# GasSensorCentral_v1_1.net
KiCad netlist of a schematic drawn in EAGLE
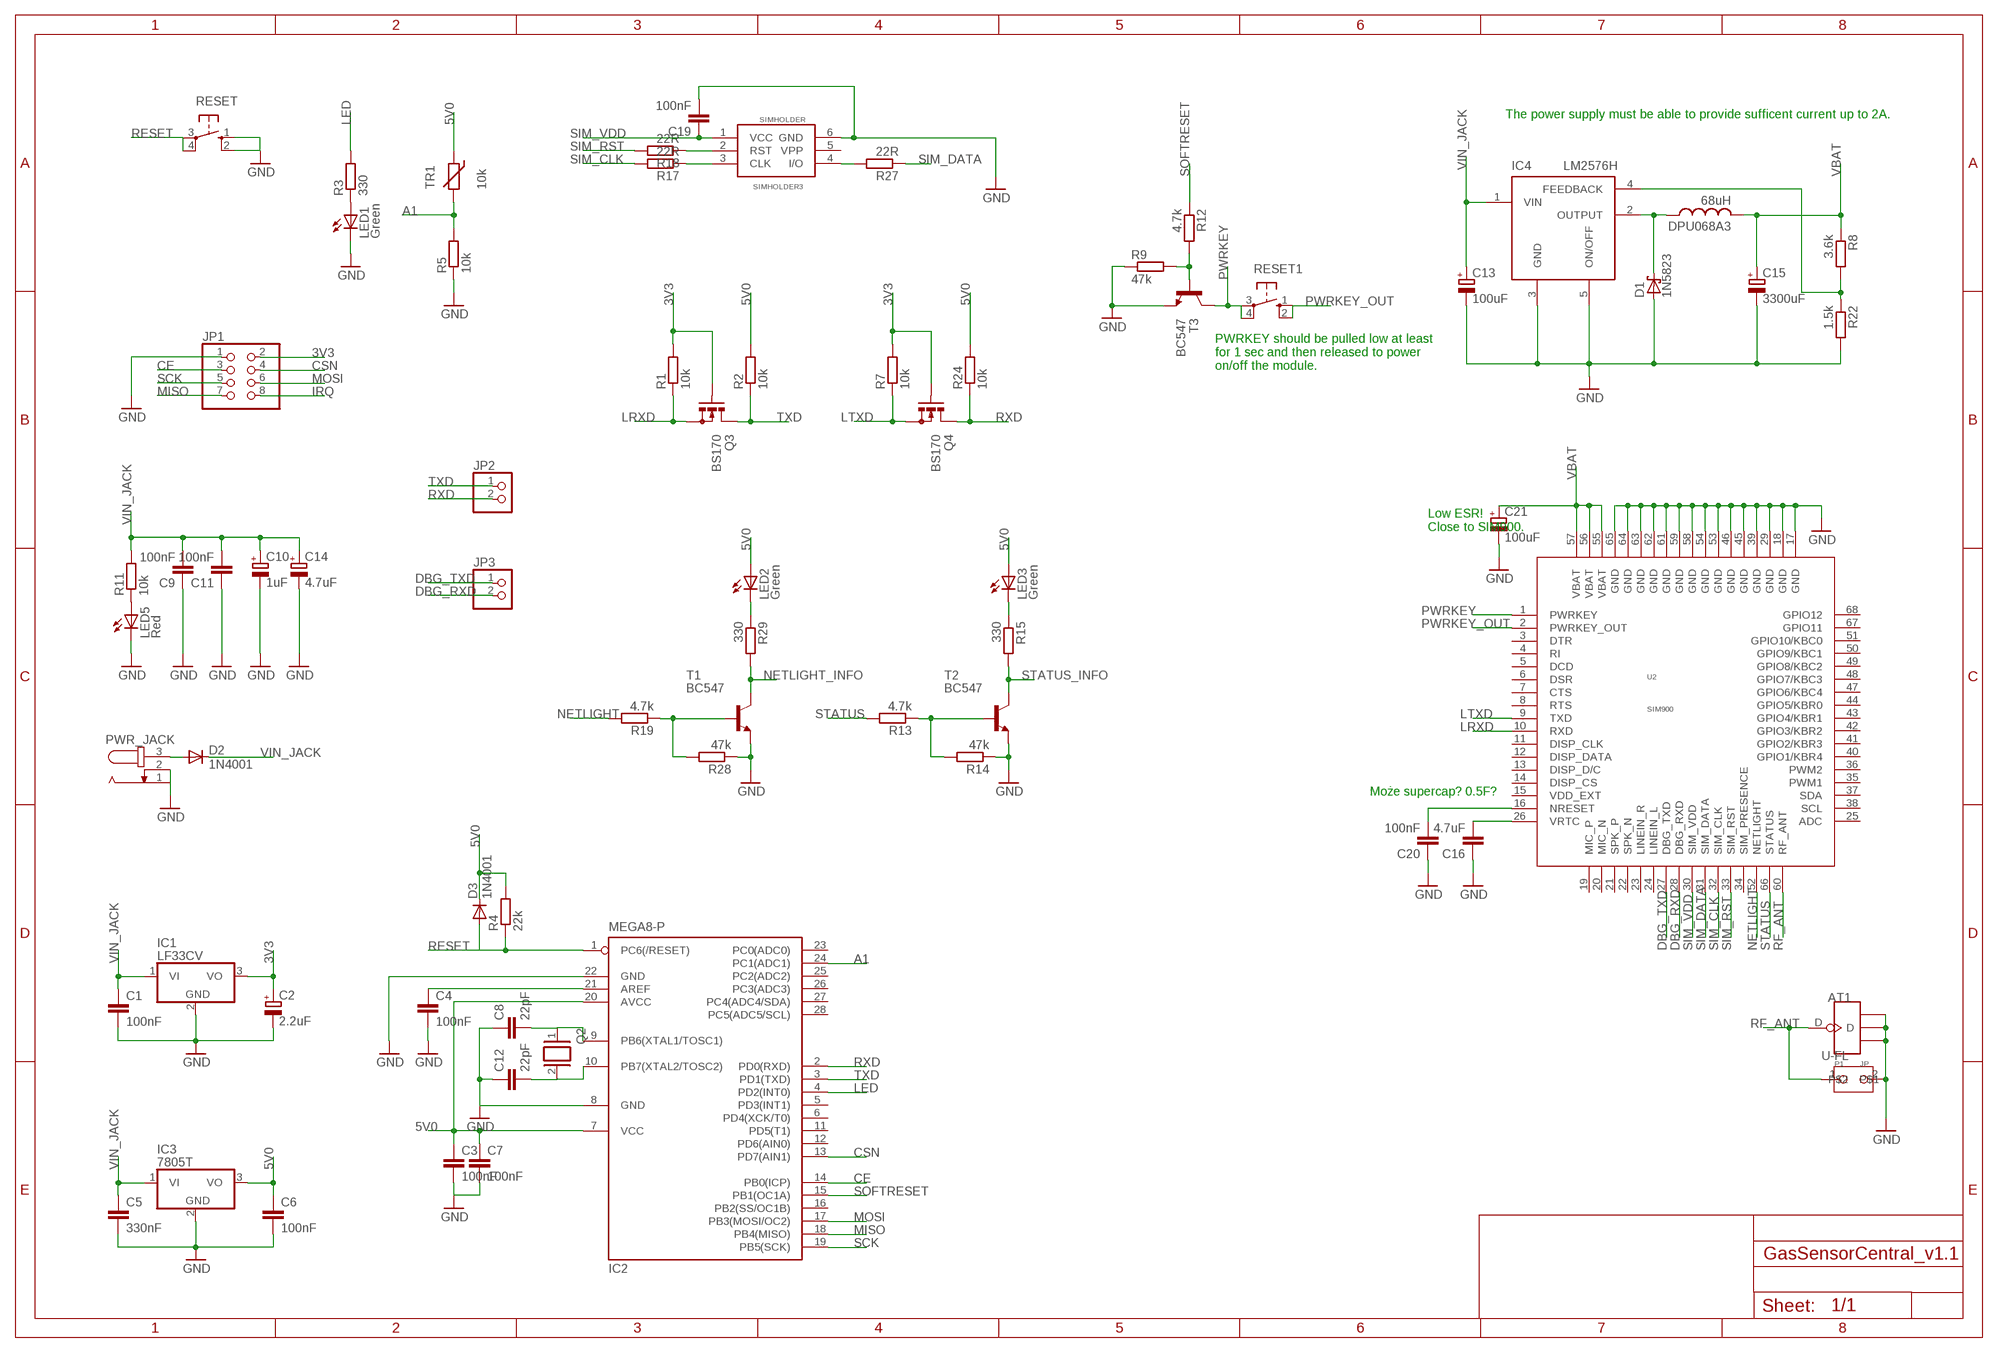
[diagram p0: schematic, sheet 1]

(export (version "E")
  (design (tool "Eeschema 10.0.6"))
  (components
    (comp (ref "AT1")
      (value "U-FL")
      (footprint "eagle-import:4P-U-FL")
      (libsource (lib "eagle-import") (part "ANTENNA-U-FL"))
    )
    (comp (ref "C1")
      (value "100nF")
      (footprint "eagle-import:C025-025X050")
      (libsource (lib "eagle-import") (part "C-EU025-025X050"))
    )
    (comp (ref "C2")
      (value "2.2uF")
      (footprint "eagle-import:E2,5-5")
      (libsource (lib "eagle-import") (part "CPOL-EUE2.5-5"))
    )
    (comp (ref "C3")
      (value "100nF")
      (footprint "eagle-import:C025-025X050")
      (libsource (lib "eagle-import") (part "C-EU025-025X050"))
    )
    (comp (ref "C4")
      (value "100nF")
      (footprint "eagle-import:C025-025X050")
      (libsource (lib "eagle-import") (part "C-EU025-025X050"))
    )
    (comp (ref "C5")
      (value "330nF")
      (footprint "eagle-import:C025-025X050")
      (libsource (lib "eagle-import") (part "C-EU025-025X050"))
    )
    (comp (ref "C6")
      (value "100nF")
      (footprint "eagle-import:C025-025X050")
      (libsource (lib "eagle-import") (part "C-EU025-025X050"))
    )
    (comp (ref "C7")
      (value "100nF")
      (footprint "eagle-import:C025-025X050")
      (libsource (lib "eagle-import") (part "C-EU025-025X050"))
    )
    (comp (ref "C8")
      (value "22pF")
      (footprint "eagle-import:C025-025X050")
      (libsource (lib "eagle-import") (part "C-EU025-025X050"))
    )
    (comp (ref "C9")
      (value "100nF")
      (footprint "eagle-import:C025-025X050")
      (libsource (lib "eagle-import") (part "C-EU025-025X050"))
    )
    (comp (ref "C10")
      (value "1uF")
      (footprint "eagle-import:E2,5-5")
      (libsource (lib "eagle-import") (part "CPOL-EUE2.5-5"))
    )
    (comp (ref "C11")
      (value "100nF")
      (footprint "eagle-import:C025-025X050")
      (libsource (lib "eagle-import") (part "C-EU025-025X050"))
    )
    (comp (ref "C12")
      (value "22pF")
      (footprint "eagle-import:C025-025X050")
      (libsource (lib "eagle-import") (part "C-EU025-025X050"))
    )
    (comp (ref "C13")
      (value "100uF")
      (footprint "eagle-import:E2,5-5")
      (libsource (lib "eagle-import") (part "CPOL-EUE2.5-5"))
    )
    (comp (ref "C14")
      (value "4.7uF")
      (footprint "eagle-import:E2,5-5")
      (libsource (lib "eagle-import") (part "CPOL-EUE2.5-5"))
    )
    (comp (ref "C15")
      (value "3300uF")
      (footprint "eagle-import:E3,5-10")
      (libsource (lib "eagle-import") (part "CPOL-EUE3.5-10"))
    )
    (comp (ref "C16")
      (value "4.7uF")
      (footprint "eagle-import:C025-025X050")
      (libsource (lib "eagle-import") (part "C-EU025-025X050"))
    )
    (comp (ref "C19")
      (value "100nF")
      (footprint "eagle-import:C025-025X050")
      (libsource (lib "eagle-import") (part "C-EU025-025X050"))
    )
    (comp (ref "C20")
      (value "100nF")
      (footprint "eagle-import:C025-025X050")
      (libsource (lib "eagle-import") (part "C-EU025-025X050"))
    )
    (comp (ref "C21")
      (value "100uF")
      (footprint "eagle-import:E2,5-5")
      (libsource (lib "eagle-import") (part "CPOL-EUE2.5-5"))
    )
    (comp (ref "D1")
      (value "1N5823")
      (footprint "eagle-import:DO41-7.6")
      (libsource (lib "eagle-import") (part "1N5817-B"))
    )
    (comp (ref "D2")
      (value "1N4001")
      (footprint "eagle-import:DO41-10")
      (libsource (lib "eagle-import") (part "1N4004"))
    )
    (comp (ref "D3")
      (value "1N4001")
      (footprint "eagle-import:DO41-10")
      (libsource (lib "eagle-import") (part "1N4004"))
    )
    (comp (ref "DPU068A3")
      (value "68uH")
      (footprint "eagle-import:TJ3-U1")
      (libsource (lib "eagle-import") (part "L-USTJ3-U1"))
    )
    (comp (ref "IC1")
      (value "LF33CV")
      (footprint "eagle-import:TO220H")
      (libsource (lib "eagle-import") (part "78T05"))
    )
    (comp (ref "IC2")
      (value "MEGA8-P")
      (footprint "eagle-import:DIL28-3")
      (libsource (lib "eagle-import") (part "MEGA8-P"))
    )
    (comp (ref "IC3")
      (value "7805T")
      (footprint "eagle-import:TO220H")
      (libsource (lib "eagle-import") (part "78T05"))
    )
    (comp (ref "IC4")
      (value "LM2576H")
      (footprint "eagle-import:TO220-52")
      (libsource (lib "eagle-import") (part "LM2576H"))
    )
    (comp (ref "JP1")
      (value "PINHD-2X4")
      (footprint "eagle-import:2X04")
      (libsource (lib "eagle-import") (part "PINHD-2X4"))
    )
    (comp (ref "JP2")
      (value "PINHD-1X2")
      (footprint "eagle-import:1X02")
      (libsource (lib "eagle-import") (part "PINHD-1X2"))
    )
    (comp (ref "JP3")
      (value "PINHD-1X2")
      (footprint "eagle-import:1X02")
      (libsource (lib "eagle-import") (part "PINHD-1X2"))
    )
    (comp (ref "LED1")
      (value "Green")
      (footprint "eagle-import:LED3MM")
      (libsource (lib "eagle-import") (part "LED3MM"))
    )
    (comp (ref "LED2")
      (value "Green")
      (footprint "eagle-import:LED3MM")
      (libsource (lib "eagle-import") (part "LED3MM"))
    )
    (comp (ref "LED3")
      (value "Green")
      (footprint "eagle-import:LED3MM")
      (libsource (lib "eagle-import") (part "LED3MM"))
    )
    (comp (ref "LED5")
      (value "Red")
      (footprint "eagle-import:LED3MM")
      (libsource (lib "eagle-import") (part "LED3MM"))
    )
    (comp (ref "P1") (value "JP") (footprint "eagle-import:JP") (libsource (lib "eagle-import") (part "JP")))
    (comp (ref "PWR_JACK")
      (value "JACK-PLUG0")
      (footprint "eagle-import:SPC4077")
      (libsource (lib "eagle-import") (part "JACK-PLUG0"))
    )
    (comp (ref "Q2")
      (value "XTAL/S")
      (footprint "eagle-import:QS")
      (libsource (lib "eagle-import") (part "XTAL/S"))
    )
    (comp (ref "Q3")
      (value "BS170")
      (footprint "eagle-import:SOT54E")
      (libsource (lib "eagle-import") (part "BS170"))
    )
    (comp (ref "Q4")
      (value "BS170")
      (footprint "eagle-import:SOT54E")
      (libsource (lib "eagle-import") (part "BS170"))
    )
    (comp (ref "R1")
      (value "10k")
      (footprint "eagle-import:0207_10")
      (libsource (lib "eagle-import") (part "R-EU_0207/10"))
    )
    (comp (ref "R2")
      (value "10k")
      (footprint "eagle-import:0207_10")
      (libsource (lib "eagle-import") (part "R-EU_0207/10"))
    )
    (comp (ref "R3")
      (value "330")
      (footprint "eagle-import:0207_10")
      (libsource (lib "eagle-import") (part "R-EU_0207/10"))
    )
    (comp (ref "R4")
      (value "22k")
      (footprint "eagle-import:0207_10")
      (libsource (lib "eagle-import") (part "R-EU_0207/10"))
    )
    (comp (ref "R5")
      (value "10k")
      (footprint "eagle-import:0207_10")
      (libsource (lib "eagle-import") (part "R-EU_0207/10"))
    )
    (comp (ref "R7")
      (value "10k")
      (footprint "eagle-import:0207_10")
      (libsource (lib "eagle-import") (part "R-EU_0207/10"))
    )
    (comp (ref "R8")
      (value "3.6k")
      (footprint "eagle-import:0207_10")
      (libsource (lib "eagle-import") (part "R-EU_0207/10"))
    )
    (comp (ref "R9")
      (value "47k")
      (footprint "eagle-import:0207_10")
      (libsource (lib "eagle-import") (part "R-EU_0207/10"))
    )
    (comp (ref "R11")
      (value "10k")
      (footprint "eagle-import:0207_10")
      (libsource (lib "eagle-import") (part "R-EU_0207/10"))
    )
    (comp (ref "R12")
      (value "4.7k")
      (footprint "eagle-import:0207_10")
      (libsource (lib "eagle-import") (part "R-EU_0207/10"))
    )
    (comp (ref "R13")
      (value "4.7k")
      (footprint "eagle-import:0207_10")
      (libsource (lib "eagle-import") (part "R-EU_0207/10"))
    )
    (comp (ref "R14")
      (value "47k")
      (footprint "eagle-import:0207_10")
      (libsource (lib "eagle-import") (part "R-EU_0207/10"))
    )
    (comp (ref "R15")
      (value "330")
      (footprint "eagle-import:0207_10")
      (libsource (lib "eagle-import") (part "R-EU_0207/10"))
    )
    (comp (ref "R17")
      (value "22R")
      (footprint "eagle-import:0207_10")
      (libsource (lib "eagle-import") (part "R-EU_0207/10"))
    )
    (comp (ref "R18")
      (value "22R")
      (footprint "eagle-import:0207_10")
      (libsource (lib "eagle-import") (part "R-EU_0207/10"))
    )
    (comp (ref "R19")
      (value "4.7k")
      (footprint "eagle-import:0207_10")
      (libsource (lib "eagle-import") (part "R-EU_0207/10"))
    )
    (comp (ref "R22")
      (value "1.5k")
      (footprint "eagle-import:0207_10")
      (libsource (lib "eagle-import") (part "R-EU_0207/10"))
    )
    (comp (ref "R24")
      (value "10k")
      (footprint "eagle-import:0207_10")
      (libsource (lib "eagle-import") (part "R-EU_0207/10"))
    )
    (comp (ref "R27")
      (value "22R")
      (footprint "eagle-import:0207_10")
      (libsource (lib "eagle-import") (part "R-EU_0207/10"))
    )
    (comp (ref "R28")
      (value "47k")
      (footprint "eagle-import:0207_10")
      (libsource (lib "eagle-import") (part "R-EU_0207/10"))
    )
    (comp (ref "R29")
      (value "330")
      (footprint "eagle-import:0207_10")
      (libsource (lib "eagle-import") (part "R-EU_0207/10"))
    )
    (comp (ref "RESET")
      (value "10-XX")
      (footprint "eagle-import:B3F-10XX")
      (fields (field (name "MPN") "B3F-1000"))
      (libsource (lib "eagle-import") (part "10-XX"))
    )
    (comp (ref "RESET1")
      (value "10-XX")
      (footprint "eagle-import:B3F-10XX")
      (fields (field (name "MPN") "B3F-1000"))
      (libsource (lib "eagle-import") (part "10-XX"))
    )
    (comp (ref "SIMHOLDER")
      (value "SIMHOLDER3")
      (footprint "eagle-import:SIMHOLDER3")
      (libsource (lib "eagle-import") (part "SIMHOLDER3"))
    )
    (comp (ref "T1")
      (value "BC547")
      (footprint "eagle-import:TO92")
      (libsource (lib "eagle-import") (part "BC547"))
    )
    (comp (ref "T2")
      (value "BC547")
      (footprint "eagle-import:TO92")
      (libsource (lib "eagle-import") (part "BC547"))
    )
    (comp (ref "T3")
      (value "BC547")
      (footprint "eagle-import:TO92")
      (libsource (lib "eagle-import") (part "BC547"))
    )
    (comp (ref "TR1")
      (value "10k")
      (footprint "eagle-import:RS-2,5")
      (libsource (lib "eagle-import") (part "THERMISTOR_R-2,5"))
    )
    (comp (ref "U2")
      (value "SIM900")
      (footprint "eagle-import:SIM900")
      (libsource (lib "eagle-import") (part "SIM900"))
    )
  )
  (nets
    (net (code "1") (name "/3V3") (class "Default")
      (node (ref "C2") (pin "+") (pinfunction "+_+") (pintype "passive"))
      (node (ref "IC1") (pin "3") (pinfunction "VO_3") (pintype "passive"))
      (node (ref "JP1") (pin "2") (pinfunction "2_2") (pintype "passive"))
      (node (ref "Q3") (pin "G") (pinfunction "G_G") (pintype "passive"))
      (node (ref "Q4") (pin "G") (pinfunction "G_G") (pintype "passive"))
      (node (ref "R1") (pin "2") (pinfunction "2_2") (pintype "passive"))
      (node (ref "R7") (pin "2") (pinfunction "2_2") (pintype "passive"))
    )
    (net (code "2") (name "/5V0") (class "Default")
      (node (ref "C3") (pin "1") (pinfunction "1_1") (pintype "passive"))
      (node (ref "C6") (pin "1") (pinfunction "1_1") (pintype "passive"))
      (node (ref "C7") (pin "1") (pinfunction "1_1") (pintype "passive"))
      (node (ref "D3") (pin "C") (pinfunction "C_C") (pintype "passive"))
      (node (ref "IC2") (pin "20") (pinfunction "AVCC_20") (pintype "power_in"))
      (node (ref "IC2") (pin "7") (pinfunction "VCC_7") (pintype "power_in"))
      (node (ref "IC3") (pin "3") (pinfunction "VO_3") (pintype "passive"))
      (node (ref "LED2") (pin "A") (pinfunction "A_A") (pintype "passive"))
      (node (ref "LED3") (pin "A") (pinfunction "A_A") (pintype "passive"))
      (node (ref "R2") (pin "2") (pinfunction "2_2") (pintype "passive"))
      (node (ref "R24") (pin "2") (pinfunction "2_2") (pintype "passive"))
      (node (ref "R4") (pin "2") (pinfunction "2_2") (pintype "passive"))
      (node (ref "TR1") (pin "1") (pinfunction "1_1") (pintype "passive"))
    )
    (net (code "3") (name "/A1") (class "Default")
      (node (ref "IC2") (pin "24") (pinfunction "PC1(ADC1)_24") (pintype "bidirectional"))
      (node (ref "R5") (pin "2") (pinfunction "2_2") (pintype "passive"))
      (node (ref "TR1") (pin "2") (pinfunction "2_2") (pintype "passive"))
    )
    (net (code "4") (name "/CE") (class "Default")
      (node (ref "IC2") (pin "14") (pinfunction "PB0(ICP)_14") (pintype "bidirectional"))
      (node (ref "JP1") (pin "3") (pinfunction "3_3") (pintype "passive"))
    )
    (net (code "5") (name "/CSN") (class "Default")
      (node (ref "IC2") (pin "13") (pinfunction "PD7(AIN1)_13") (pintype "bidirectional"))
      (node (ref "JP1") (pin "4") (pinfunction "4_4") (pintype "passive"))
    )
    (net (code "6") (name "/DBG_RXD") (class "Default")
      (node (ref "JP3") (pin "2") (pinfunction "2_2") (pintype "passive"))
      (node (ref "U2") (pin "28") (pinfunction "DBG_RXD_28") (pintype "input"))
    )
    (net (code "7") (name "/DBG_TXD") (class "Default")
      (node (ref "JP3") (pin "1") (pinfunction "1_1") (pintype "passive"))
      (node (ref "U2") (pin "27") (pinfunction "DBG_TXD_27") (pintype "output"))
    )
    (net (code "8") (name "/IRQ") (class "Default")
      (node (ref "JP1") (pin "8") (pinfunction "8_8") (pintype "passive"))
    )
    (net (code "9") (name "/LED") (class "Default")
      (node (ref "IC2") (pin "4") (pinfunction "PD2(INT0)_4") (pintype "bidirectional"))
      (node (ref "R3") (pin "2") (pinfunction "2_2") (pintype "passive"))
    )
    (net (code "10") (name "/LRXD") (class "Default")
      (node (ref "Q3") (pin "S") (pinfunction "S_S") (pintype "passive"))
      (node (ref "R1") (pin "1") (pinfunction "1_1") (pintype "passive"))
      (node (ref "U2") (pin "10") (pinfunction "RXD_10") (pintype "input"))
    )
    (net (code "11") (name "/LTXD") (class "Default")
      (node (ref "Q4") (pin "S") (pinfunction "S_S") (pintype "passive"))
      (node (ref "R7") (pin "1") (pinfunction "1_1") (pintype "passive"))
      (node (ref "U2") (pin "9") (pinfunction "TXD_9") (pintype "output"))
    )
    (net (code "12") (name "/MISO") (class "Default")
      (node (ref "IC2") (pin "18") (pinfunction "PB4(MISO)_18") (pintype "bidirectional"))
      (node (ref "JP1") (pin "7") (pinfunction "7_7") (pintype "passive"))
    )
    (net (code "13") (name "/MOSI") (class "Default")
      (node (ref "IC2") (pin "17") (pinfunction "PB3(MOSI/OC2)_17") (pintype "bidirectional"))
      (node (ref "JP1") (pin "6") (pinfunction "6_6") (pintype "passive"))
    )
    (net (code "14") (name "/NETLIGHT") (class "Default")
      (node (ref "R19") (pin "2") (pinfunction "2_2") (pintype "passive"))
      (node (ref "U2") (pin "52") (pinfunction "NETLIGHT_52") (pintype "output"))
    )
    (net (code "15") (name "/NETLIGHT_INFO") (class "Default")
      (node (ref "R29") (pin "2") (pinfunction "2_2") (pintype "passive"))
      (node (ref "T1") (pin "3") (pinfunction "C_3") (pintype "passive"))
    )
    (net (code "16") (name "/PWRKEY") (class "Default")
      (node (ref "RESET1") (pin "3") (pinfunction "P_3") (pintype "passive"))
      (node (ref "RESET1") (pin "4") (pinfunction "P1_4") (pintype "passive"))
      (node (ref "T3") (pin "3") (pinfunction "C_3") (pintype "passive"))
      (node (ref "U2") (pin "1") (pinfunction "PWRKEY_1") (pintype "input"))
    )
    (net (code "17") (name "/PWRKEY_OUT") (class "Default")
      (node (ref "RESET1") (pin "1") (pinfunction "S_1") (pintype "passive"))
      (node (ref "RESET1") (pin "2") (pinfunction "S1_2") (pintype "passive"))
      (node (ref "U2") (pin "2") (pinfunction "PWRKEY_OUT_2") (pintype "output"))
    )
    (net (code "18") (name "/RESET") (class "Default")
      (node (ref "D3") (pin "A") (pinfunction "A_A") (pintype "passive"))
      (node (ref "IC2") (pin "1") (pinfunction "PC6(/RESET)_1") (pintype "bidirectional"))
      (node (ref "R4") (pin "1") (pinfunction "1_1") (pintype "passive"))
      (node (ref "RESET") (pin "3") (pinfunction "P_3") (pintype "passive"))
      (node (ref "RESET") (pin "4") (pinfunction "P1_4") (pintype "passive"))
    )
    (net (code "19") (name "/RF_ANT") (class "Default")
      (node (ref "AT1") (pin "D") (pinfunction "D_D") (pintype "bidirectional"))
      (node (ref "P1") (pin "1") (pinfunction "P$1_1") (pintype "bidirectional"))
      (node (ref "U2") (pin "60") (pinfunction "RF_ANT_60") (pintype "bidirectional"))
    )
    (net (code "20") (name "/RXD") (class "Default")
      (node (ref "IC2") (pin "2") (pinfunction "PD0(RXD)_2") (pintype "bidirectional"))
      (node (ref "JP2") (pin "2") (pinfunction "2_2") (pintype "passive"))
      (node (ref "Q4") (pin "D") (pinfunction "D_D") (pintype "passive"))
      (node (ref "R24") (pin "1") (pinfunction "1_1") (pintype "passive"))
    )
    (net (code "21") (name "/SCK") (class "Default")
      (node (ref "IC2") (pin "19") (pinfunction "PB5(SCK)_19") (pintype "bidirectional"))
      (node (ref "JP1") (pin "5") (pinfunction "5_5") (pintype "passive"))
    )
    (net (code "22") (name "/SIM_CLK") (class "Default")
      (node (ref "R17") (pin "2") (pinfunction "2_2") (pintype "passive"))
      (node (ref "U2") (pin "32") (pinfunction "SIM_CLK_32") (pintype "output"))
    )
    (net (code "23") (name "/SIM_DATA") (class "Default")
      (node (ref "R27") (pin "1") (pinfunction "1_1") (pintype "passive"))
      (node (ref "U2") (pin "31") (pinfunction "SIM_DATA_31") (pintype "bidirectional"))
    )
    (net (code "24") (name "/SIM_RST") (class "Default")
      (node (ref "R18") (pin "2") (pinfunction "2_2") (pintype "passive"))
      (node (ref "U2") (pin "33") (pinfunction "SIM_RST_33") (pintype "output"))
    )
    (net (code "25") (name "/SIM_VDD") (class "Default")
      (node (ref "C19") (pin "1") (pinfunction "1_1") (pintype "passive"))
      (node (ref "SIMHOLDER") (pin "1") (pinfunction "VCC_1") (pintype "bidirectional"))
      (node (ref "U2") (pin "30") (pinfunction "SIM_VDD_30") (pintype "output"))
    )
    (net (code "26") (name "/SOFTRESET") (class "Default")
      (node (ref "IC2") (pin "15") (pinfunction "PB1(OC1A)_15") (pintype "bidirectional"))
      (node (ref "R12") (pin "1") (pinfunction "1_1") (pintype "passive"))
    )
    (net (code "27") (name "/STATUS") (class "Default")
      (node (ref "R13") (pin "2") (pinfunction "2_2") (pintype "passive"))
      (node (ref "U2") (pin "66") (pinfunction "STATUS_66") (pintype "output"))
    )
    (net (code "28") (name "/STATUS_INFO") (class "Default")
      (node (ref "R15") (pin "2") (pinfunction "2_2") (pintype "passive"))
      (node (ref "T2") (pin "3") (pinfunction "C_3") (pintype "passive"))
    )
    (net (code "29") (name "/TXD") (class "Default")
      (node (ref "IC2") (pin "3") (pinfunction "PD1(TXD)_3") (pintype "bidirectional"))
      (node (ref "JP2") (pin "1") (pinfunction "1_1") (pintype "passive"))
      (node (ref "Q3") (pin "D") (pinfunction "D_D") (pintype "passive"))
      (node (ref "R2") (pin "1") (pinfunction "1_1") (pintype "passive"))
    )
    (net (code "30") (name "/VBAT") (class "Default")
      (node (ref "C15") (pin "+") (pinfunction "+_+") (pintype "passive"))
      (node (ref "C21") (pin "+") (pinfunction "+_+") (pintype "passive"))
      (node (ref "DPU068A3") (pin "2") (pinfunction "2_2") (pintype "passive"))
      (node (ref "R8") (pin "1") (pinfunction "1_1") (pintype "passive"))
      (node (ref "U2") (pin "55") (pinfunction "VBAT_55") (pintype "power_in"))
      (node (ref "U2") (pin "56") (pinfunction "VBAT_56") (pintype "power_in"))
      (node (ref "U2") (pin "57") (pinfunction "VBAT_57") (pintype "power_in"))
    )
    (net (code "31") (name "/VIN_JACK") (class "Default")
      (node (ref "C1") (pin "1") (pinfunction "1_1") (pintype "passive"))
      (node (ref "C10") (pin "+") (pinfunction "+_+") (pintype "passive"))
      (node (ref "C11") (pin "2") (pinfunction "2_2") (pintype "passive"))
      (node (ref "C13") (pin "+") (pinfunction "+_+") (pintype "passive"))
      (node (ref "C14") (pin "+") (pinfunction "+_+") (pintype "passive"))
      (node (ref "C5") (pin "1") (pinfunction "1_1") (pintype "passive"))
      (node (ref "C9") (pin "2") (pinfunction "2_2") (pintype "passive"))
      (node (ref "D2") (pin "C") (pinfunction "C_C") (pintype "passive"))
      (node (ref "IC1") (pin "1") (pinfunction "VI_1") (pintype "input"))
      (node (ref "IC3") (pin "1") (pinfunction "VI_1") (pintype "input"))
      (node (ref "IC4") (pin "1") (pinfunction "VIN_1") (pintype "input"))
      (node (ref "R11") (pin "2") (pinfunction "2_2") (pintype "passive"))
    )
    (net (code "32") (name "GND") (class "Default")
      (node (ref "AT1") (pin "GND1") (pinfunction "GND1_GND1") (pintype "bidirectional"))
      (node (ref "AT1") (pin "GND2") (pinfunction "GND2_GND2") (pintype "bidirectional"))
      (node (ref "AT1") (pin "GND3") (pinfunction "GND3_GND3") (pintype "bidirectional"))
      (node (ref "C1") (pin "2") (pinfunction "2_2") (pintype "passive"))
      (node (ref "C10") (pin "-") (pinfunction "-_-") (pintype "passive"))
      (node (ref "C11") (pin "1") (pinfunction "1_1") (pintype "passive"))
      (node (ref "C12") (pin "1") (pinfunction "1_1") (pintype "passive"))
      (node (ref "C13") (pin "-") (pinfunction "-_-") (pintype "passive"))
      (node (ref "C14") (pin "-") (pinfunction "-_-") (pintype "passive"))
      (node (ref "C15") (pin "-") (pinfunction "-_-") (pintype "passive"))
      (node (ref "C16") (pin "1") (pinfunction "1_1") (pintype "passive"))
      (node (ref "C19") (pin "2") (pinfunction "2_2") (pintype "passive"))
      (node (ref "C2") (pin "-") (pinfunction "-_-") (pintype "passive"))
      (node (ref "C20") (pin "1") (pinfunction "1_1") (pintype "passive"))
      (node (ref "C21") (pin "-") (pinfunction "-_-") (pintype "passive"))
      (node (ref "C3") (pin "2") (pinfunction "2_2") (pintype "passive"))
      (node (ref "C4") (pin "2") (pinfunction "2_2") (pintype "passive"))
      (node (ref "C5") (pin "2") (pinfunction "2_2") (pintype "passive"))
      (node (ref "C6") (pin "2") (pinfunction "2_2") (pintype "passive"))
      (node (ref "C7") (pin "2") (pinfunction "2_2") (pintype "passive"))
      (node (ref "C8") (pin "1") (pinfunction "1_1") (pintype "passive"))
      (node (ref "C9") (pin "1") (pinfunction "1_1") (pintype "passive"))
      (node (ref "D1") (pin "A") (pinfunction "A_A") (pintype "passive"))
      (node (ref "IC1") (pin "2") (pinfunction "GND_2") (pintype "passive"))
      (node (ref "IC2") (pin "22") (pinfunction "GND_22") (pintype "power_in"))
      (node (ref "IC2") (pin "8") (pinfunction "GND_8") (pintype "power_in"))
      (node (ref "IC3") (pin "2") (pinfunction "GND_2") (pintype "passive"))
      (node (ref "IC4") (pin "3") (pinfunction "GND_3") (pintype "power_in"))
      (node (ref "IC4") (pin "5") (pinfunction "ON/OFF_5") (pintype "bidirectional"))
      (node (ref "JP1") (pin "1") (pinfunction "1_1") (pintype "passive"))
      (node (ref "LED1") (pin "K") (pinfunction "C_K") (pintype "passive"))
      (node (ref "LED5") (pin "K") (pinfunction "C_K") (pintype "passive"))
      (node (ref "P1") (pin "2") (pinfunction "P$2_2") (pintype "bidirectional"))
      (node (ref "PWR_JACK") (pin "1") (pinfunction "1_1") (pintype "passive"))
      (node (ref "PWR_JACK") (pin "2") (pinfunction "2_2") (pintype "passive"))
      (node (ref "R14") (pin "1") (pinfunction "1_1") (pintype "passive"))
      (node (ref "R22") (pin "2") (pinfunction "2_2") (pintype "passive"))
      (node (ref "R28") (pin "1") (pinfunction "1_1") (pintype "passive"))
      (node (ref "R5") (pin "1") (pinfunction "1_1") (pintype "passive"))
      (node (ref "R9") (pin "1") (pinfunction "1_1") (pintype "passive"))
      (node (ref "RESET") (pin "1") (pinfunction "S_1") (pintype "passive"))
      (node (ref "RESET") (pin "2") (pinfunction "S1_2") (pintype "passive"))
      (node (ref "SIMHOLDER") (pin "6") (pinfunction "GND_6") (pintype "bidirectional"))
      (node (ref "T1") (pin "1") (pinfunction "E_1") (pintype "passive"))
      (node (ref "T2") (pin "1") (pinfunction "E_1") (pintype "passive"))
      (node (ref "T3") (pin "1") (pinfunction "E_1") (pintype "passive"))
      (node (ref "U2") (pin "17") (pinfunction "GND_17") (pintype "power_in"))
      (node (ref "U2") (pin "18") (pinfunction "GND_18") (pintype "power_in"))
      (node (ref "U2") (pin "29") (pinfunction "GND_29") (pintype "power_in"))
      (node (ref "U2") (pin "39") (pinfunction "GND_39") (pintype "power_in"))
      (node (ref "U2") (pin "45") (pinfunction "GND_45") (pintype "power_in"))
      (node (ref "U2") (pin "46") (pinfunction "GND_46") (pintype "power_in"))
      (node (ref "U2") (pin "53") (pinfunction "GND_53") (pintype "power_in"))
      (node (ref "U2") (pin "54") (pinfunction "GND_54") (pintype "power_in"))
      (node (ref "U2") (pin "58") (pinfunction "GND_58") (pintype "power_in"))
      (node (ref "U2") (pin "59") (pinfunction "GND_59") (pintype "power_in"))
      (node (ref "U2") (pin "61") (pinfunction "GND_61") (pintype "power_in"))
      (node (ref "U2") (pin "62") (pinfunction "GND_62") (pintype "power_in"))
      (node (ref "U2") (pin "63") (pinfunction "GND_63") (pintype "power_in"))
      (node (ref "U2") (pin "64") (pinfunction "GND_64") (pintype "power_in"))
      (node (ref "U2") (pin "65") (pinfunction "GND_65") (pintype "power_in"))
    )
    (net (code "33") (name "Net-(D2-PadA)") (class "Default")
      (node (ref "D2") (pin "A") (pinfunction "A_A") (pintype "passive"))
      (node (ref "PWR_JACK") (pin "3") (pinfunction "3_3") (pintype "passive"))
    )
    (net (code "34") (name "Net-(IC2-AREF)") (class "Default")
      (node (ref "C4") (pin "1") (pinfunction "1_1") (pintype "passive"))
      (node (ref "IC2") (pin "21") (pinfunction "AREF_21") (pintype "passive"))
    )
    (net (code "35") (name "Net-(IC2-PB6(XTAL1{slash}TOSC1))") (class "Default")
      (node (ref "C8") (pin "2") (pinfunction "2_2") (pintype "passive"))
      (node (ref "IC2") (pin "9") (pinfunction "PB6(XTAL1/TOSC1)_9") (pintype "bidirectional"))
      (node (ref "Q2") (pin "1") (pinfunction "1_1") (pintype "passive"))
    )
    (net (code "36") (name "Net-(IC2-PB7(XTAL2{slash}TOSC2))") (class "Default")
      (node (ref "C12") (pin "2") (pinfunction "2_2") (pintype "passive"))
      (node (ref "IC2") (pin "10") (pinfunction "PB7(XTAL2/TOSC2)_10") (pintype "bidirectional"))
      (node (ref "Q2") (pin "2") (pinfunction "2_2") (pintype "passive"))
    )
    (net (code "37") (name "Net-(IC4-FEEDBACK)") (class "Default")
      (node (ref "IC4") (pin "4") (pinfunction "FEEDBACK_4") (pintype "bidirectional"))
      (node (ref "R22") (pin "1") (pinfunction "1_1") (pintype "passive"))
      (node (ref "R8") (pin "2") (pinfunction "2_2") (pintype "passive"))
    )
    (net (code "38") (name "Net-(IC4-OUTPUT)") (class "Default")
      (node (ref "D1") (pin "C") (pinfunction "C_C") (pintype "passive"))
      (node (ref "DPU068A3") (pin "1") (pinfunction "1_1") (pintype "passive"))
      (node (ref "IC4") (pin "2") (pinfunction "OUTPUT_2") (pintype "output"))
    )
    (net (code "39") (name "Net-(LED1-PadA)") (class "Default")
      (node (ref "LED1") (pin "A") (pinfunction "A_A") (pintype "passive"))
      (node (ref "R3") (pin "1") (pinfunction "1_1") (pintype "passive"))
    )
    (net (code "40") (name "Net-(LED2-C)") (class "Default")
      (node (ref "LED2") (pin "K") (pinfunction "C_K") (pintype "passive"))
      (node (ref "R29") (pin "1") (pinfunction "1_1") (pintype "passive"))
    )
    (net (code "41") (name "Net-(LED3-C)") (class "Default")
      (node (ref "LED3") (pin "K") (pinfunction "C_K") (pintype "passive"))
      (node (ref "R15") (pin "1") (pinfunction "1_1") (pintype "passive"))
    )
    (net (code "42") (name "Net-(LED5-PadA)") (class "Default")
      (node (ref "LED5") (pin "A") (pinfunction "A_A") (pintype "passive"))
      (node (ref "R11") (pin "1") (pinfunction "1_1") (pintype "passive"))
    )
    (net (code "43") (name "Net-(SIMHOLDER-CLK)") (class "Default")
      (node (ref "R17") (pin "1") (pinfunction "1_1") (pintype "passive"))
      (node (ref "SIMHOLDER") (pin "3") (pinfunction "CLK_3") (pintype "bidirectional"))
    )
    (net (code "44") (name "Net-(SIMHOLDER-I{slash}O)") (class "Default")
      (node (ref "R27") (pin "2") (pinfunction "2_2") (pintype "passive"))
      (node (ref "SIMHOLDER") (pin "4") (pinfunction "I/O_4") (pintype "bidirectional"))
    )
    (net (code "45") (name "Net-(SIMHOLDER-RST)") (class "Default")
      (node (ref "R18") (pin "1") (pinfunction "1_1") (pintype "passive"))
      (node (ref "SIMHOLDER") (pin "2") (pinfunction "RST_2") (pintype "bidirectional"))
    )
    (net (code "46") (name "Net-(T1-B)") (class "Default")
      (node (ref "R19") (pin "1") (pinfunction "1_1") (pintype "passive"))
      (node (ref "R28") (pin "2") (pinfunction "2_2") (pintype "passive"))
      (node (ref "T1") (pin "2") (pinfunction "B_2") (pintype "passive"))
    )
    (net (code "47") (name "Net-(T2-B)") (class "Default")
      (node (ref "R13") (pin "1") (pinfunction "1_1") (pintype "passive"))
      (node (ref "R14") (pin "2") (pinfunction "2_2") (pintype "passive"))
      (node (ref "T2") (pin "2") (pinfunction "B_2") (pintype "passive"))
    )
    (net (code "48") (name "Net-(T3-B)") (class "Default")
      (node (ref "R12") (pin "2") (pinfunction "2_2") (pintype "passive"))
      (node (ref "R9") (pin "2") (pinfunction "2_2") (pintype "passive"))
      (node (ref "T3") (pin "2") (pinfunction "B_2") (pintype "passive"))
    )
    (net (code "49") (name "Net-(U2-NRESET)") (class "Default")
      (node (ref "C20") (pin "2") (pinfunction "2_2") (pintype "passive"))
      (node (ref "U2") (pin "16") (pinfunction "NRESET_16") (pintype "input"))
    )
    (net (code "50") (name "Net-(U2-VRTC)") (class "Default")
      (node (ref "C16") (pin "2") (pinfunction "2_2") (pintype "passive"))
      (node (ref "U2") (pin "26") (pinfunction "VRTC_26") (pintype "bidirectional"))
    )
    (net (code "51") (name "unconnected-(IC2-PB2(SS{slash}OC1B)-Pad16)") (class "Default")
      (node (ref "IC2") (pin "16") (pinfunction "PB2(SS/OC1B)_16") (pintype "bidirectional"))
    )
    (net (code "52") (name "unconnected-(IC2-PC0(ADC0)-Pad23)") (class "Default")
      (node (ref "IC2") (pin "23") (pinfunction "PC0(ADC0)_23") (pintype "bidirectional"))
    )
    (net (code "53") (name "unconnected-(IC2-PC2(ADC2)-Pad25)") (class "Default")
      (node (ref "IC2") (pin "25") (pinfunction "PC2(ADC2)_25") (pintype "bidirectional"))
    )
    (net (code "54") (name "unconnected-(IC2-PC3(ADC3)-Pad26)") (class "Default")
      (node (ref "IC2") (pin "26") (pinfunction "PC3(ADC3)_26") (pintype "bidirectional"))
    )
    (net (code "55") (name "unconnected-(IC2-PC4(ADC4{slash}SDA)-Pad27)") (class "Default")
      (node (ref "IC2") (pin "27") (pinfunction "PC4(ADC4/SDA)_27") (pintype "bidirectional"))
    )
    (net (code "56") (name "unconnected-(IC2-PC5(ADC5{slash}SCL)-Pad28)") (class "Default")
      (node (ref "IC2") (pin "28") (pinfunction "PC5(ADC5/SCL)_28") (pintype "bidirectional"))
    )
    (net (code "57") (name "unconnected-(IC2-PD3(INT1)-Pad5)") (class "Default")
      (node (ref "IC2") (pin "5") (pinfunction "PD3(INT1)_5") (pintype "bidirectional"))
    )
    (net (code "58") (name "unconnected-(IC2-PD4(XCK{slash}T0)-Pad6)") (class "Default")
      (node (ref "IC2") (pin "6") (pinfunction "PD4(XCK/T0)_6") (pintype "bidirectional"))
    )
    (net (code "59") (name "unconnected-(IC2-PD5(T1)-Pad11)") (class "Default")
      (node (ref "IC2") (pin "11") (pinfunction "PD5(T1)_11") (pintype "bidirectional"))
    )
    (net (code "60") (name "unconnected-(IC2-PD6(AIN0)-Pad12)") (class "Default")
      (node (ref "IC2") (pin "12") (pinfunction "PD6(AIN0)_12") (pintype "bidirectional"))
    )
    (net (code "61") (name "unconnected-(SIMHOLDER-VPP-Pad5)") (class "Default")
      (node (ref "SIMHOLDER") (pin "5") (pinfunction "VPP_5") (pintype "bidirectional"))
    )
    (net (code "62") (name "unconnected-(U2-ADC-Pad25)") (class "Default")
      (node (ref "U2") (pin "25") (pinfunction "ADC_25") (pintype "input"))
    )
    (net (code "63") (name "unconnected-(U2-CTS-Pad7)") (class "Default")
      (node (ref "U2") (pin "7") (pinfunction "CTS_7") (pintype "output"))
    )
    (net (code "64") (name "unconnected-(U2-DCD-Pad5)") (class "Default")
      (node (ref "U2") (pin "5") (pinfunction "DCD_5") (pintype "output"))
    )
    (net (code "65") (name "unconnected-(U2-DISP_CLK-Pad11)") (class "Default")
      (node (ref "U2") (pin "11") (pinfunction "DISP_CLK_11") (pintype "output"))
    )
    (net (code "66") (name "unconnected-(U2-DISP_CS-Pad14)") (class "Default")
      (node (ref "U2") (pin "14") (pinfunction "DISP_CS_14") (pintype "output"))
    )
    (net (code "67") (name "unconnected-(U2-DISP_DATA-Pad12)") (class "Default")
      (node (ref "U2") (pin "12") (pinfunction "DISP_DATA_12") (pintype "bidirectional"))
    )
    (net (code "68") (name "unconnected-(U2-DISP_D{slash}C-Pad13)") (class "Default")
      (node (ref "U2") (pin "13") (pinfunction "DISP_D/C_13") (pintype "output"))
    )
    (net (code "69") (name "unconnected-(U2-DSR-Pad6)") (class "Default")
      (node (ref "U2") (pin "6") (pinfunction "DSR_6") (pintype "output"))
    )
    (net (code "70") (name "unconnected-(U2-DTR-Pad3)") (class "Default")
      (node (ref "U2") (pin "3") (pinfunction "DTR_3") (pintype "input"))
    )
    (net (code "71") (name "unconnected-(U2-GPIO1{slash}KBR4-Pad40)") (class "Default")
      (node (ref "U2") (pin "40") (pinfunction "GPIO1/KBR4_40") (pintype "output"))
    )
    (net (code "72") (name "unconnected-(U2-GPIO2{slash}KBR3-Pad41)") (class "Default")
      (node (ref "U2") (pin "41") (pinfunction "GPIO2/KBR3_41") (pintype "output"))
    )
    (net (code "73") (name "unconnected-(U2-GPIO3{slash}KBR2-Pad42)") (class "Default")
      (node (ref "U2") (pin "42") (pinfunction "GPIO3/KBR2_42") (pintype "output"))
    )
    (net (code "74") (name "unconnected-(U2-GPIO4{slash}KBR1-Pad43)") (class "Default")
      (node (ref "U2") (pin "43") (pinfunction "GPIO4/KBR1_43") (pintype "output"))
    )
    (net (code "75") (name "unconnected-(U2-GPIO5{slash}KBR0-Pad44)") (class "Default")
      (node (ref "U2") (pin "44") (pinfunction "GPIO5/KBR0_44") (pintype "output"))
    )
    (net (code "76") (name "unconnected-(U2-GPIO6{slash}KBC4-Pad47)") (class "Default")
      (node (ref "U2") (pin "47") (pinfunction "GPIO6/KBC4_47") (pintype "input"))
    )
    (net (code "77") (name "unconnected-(U2-GPIO7{slash}KBC3-Pad48)") (class "Default")
      (node (ref "U2") (pin "48") (pinfunction "GPIO7/KBC3_48") (pintype "bidirectional"))
    )
    (net (code "78") (name "unconnected-(U2-GPIO8{slash}KBC2-Pad49)") (class "Default")
      (node (ref "U2") (pin "49") (pinfunction "GPIO8/KBC2_49") (pintype "input"))
    )
    (net (code "79") (name "unconnected-(U2-GPIO9{slash}KBC1-Pad50)") (class "Default")
      (node (ref "U2") (pin "50") (pinfunction "GPIO9/KBC1_50") (pintype "input"))
    )
    (net (code "80") (name "unconnected-(U2-GPIO10{slash}KBC0-Pad51)") (class "Default")
      (node (ref "U2") (pin "51") (pinfunction "GPIO10/KBC0_51") (pintype "bidirectional"))
    )
    (net (code "81") (name "unconnected-(U2-GPIO11-Pad67)") (class "Default")
      (node (ref "U2") (pin "67") (pinfunction "GPIO11_67") (pintype "bidirectional"))
    )
    (net (code "82") (name "unconnected-(U2-GPIO12-Pad68)") (class "Default")
      (node (ref "U2") (pin "68") (pinfunction "GPIO12_68") (pintype "bidirectional"))
    )
    (net (code "83") (name "unconnected-(U2-LINEIN_L-Pad24)") (class "Default")
      (node (ref "U2") (pin "24") (pinfunction "LINEIN_L_24") (pintype "input"))
    )
    (net (code "84") (name "unconnected-(U2-LINEIN_R-Pad23)") (class "Default")
      (node (ref "U2") (pin "23") (pinfunction "LINEIN_R_23") (pintype "input"))
    )
    (net (code "85") (name "unconnected-(U2-MIC_N-Pad20)") (class "Default")
      (node (ref "U2") (pin "20") (pinfunction "MIC_N_20") (pintype "input"))
    )
    (net (code "86") (name "unconnected-(U2-MIC_P-Pad19)") (class "Default")
      (node (ref "U2") (pin "19") (pinfunction "MIC_P_19") (pintype "input"))
    )
    (net (code "87") (name "unconnected-(U2-PWM1-Pad35)") (class "Default")
      (node (ref "U2") (pin "35") (pinfunction "PWM1_35") (pintype "output"))
    )
    (net (code "88") (name "unconnected-(U2-PWM2-Pad36)") (class "Default")
      (node (ref "U2") (pin "36") (pinfunction "PWM2_36") (pintype "output"))
    )
    (net (code "89") (name "unconnected-(U2-RI-Pad4)") (class "Default")
      (node (ref "U2") (pin "4") (pinfunction "RI_4") (pintype "output"))
    )
    (net (code "90") (name "unconnected-(U2-RTS-Pad8)") (class "Default")
      (node (ref "U2") (pin "8") (pinfunction "RTS_8") (pintype "input"))
    )
    (net (code "91") (name "unconnected-(U2-SCL-Pad38)") (class "Default")
      (node (ref "U2") (pin "38") (pinfunction "SCL_38") (pintype "output"))
    )
    (net (code "92") (name "unconnected-(U2-SDA-Pad37)") (class "Default")
      (node (ref "U2") (pin "37") (pinfunction "SDA_37") (pintype "bidirectional"))
    )
    (net (code "93") (name "unconnected-(U2-SIM_PRESENCE-Pad34)") (class "Default")
      (node (ref "U2") (pin "34") (pinfunction "SIM_PRESENCE_34") (pintype "input"))
    )
    (net (code "94") (name "unconnected-(U2-SPK_N-Pad22)") (class "Default")
      (node (ref "U2") (pin "22") (pinfunction "SPK_N_22") (pintype "output"))
    )
    (net (code "95") (name "unconnected-(U2-SPK_P-Pad21)") (class "Default")
      (node (ref "U2") (pin "21") (pinfunction "SPK_P_21") (pintype "output"))
    )
    (net (code "96") (name "unconnected-(U2-VDD_EXT-Pad15)") (class "Default")
      (node (ref "U2") (pin "15") (pinfunction "VDD_EXT_15") (pintype "output"))
    )
  )
)
